# GSM_PPS_LED_Driver.net
KiCad netlist of a schematic drawn in Altium Designer
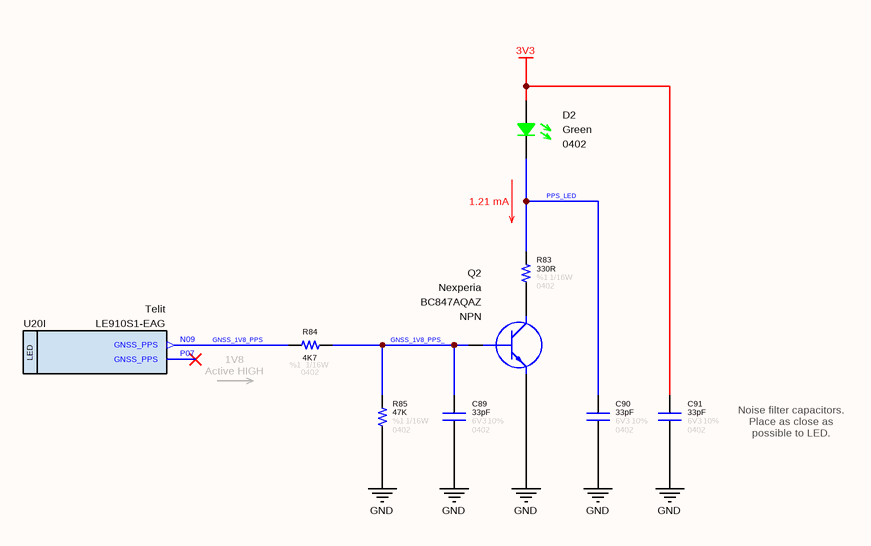
[diagram p0: GSM PPS LED Driver.SchDoc]

(export (version "E")
  (design (tool "Eeschema 10.0.6"))
  (components
    (comp (ref "C89")
      (value "33pF")
      (footprint "CAPACITOR_0402")
      (description "Capacitor - 33pF [0402] (Ceramic)")
      (fields
        (field (name "MANUFACTURER PART NUMBER") "C0402C330J9RACAUTO")
        (field (name "TOLERANCE") "10%")
        (field (name "CASE") "0402")
        (field (name "VOLTAGE") "6V3")
      )
      (libsource (lib "Akkoyun") (part "Capacitor - 33pF [0402-6V3]"))
    )
    (comp (ref "C90")
      (value "33pF")
      (footprint "CAPACITOR_0402")
      (description "Capacitor - 33pF [0402] (Ceramic)")
      (fields
        (field (name "MANUFACTURER PART NUMBER") "C0402C330J9RACAUTO")
        (field (name "TOLERANCE") "10%")
        (field (name "CASE") "0402")
        (field (name "VOLTAGE") "6V3")
      )
      (libsource (lib "Akkoyun") (part "Capacitor - 33pF [0402-6V3]"))
    )
    (comp (ref "C91")
      (value "33pF")
      (footprint "CAPACITOR_0402")
      (description "Capacitor - 33pF [0402] (Ceramic)")
      (fields
        (field (name "MANUFACTURER PART NUMBER") "C0402C330J9RACAUTO")
        (field (name "TOLERANCE") "10%")
        (field (name "CASE") "0402")
        (field (name "VOLTAGE") "6V3")
      )
      (libsource (lib "Akkoyun") (part "Capacitor - 33pF [0402-6V3]"))
    )
    (comp (ref "D2")
      (value "SMD LED (Green)")
      (footprint "LED_0402")
      (description "Standard LEDs - SMD MINI-MOLD ULTRA COMPACT GREEN")
      (fields
        (field (name "MANUFACTURER PART NUMBER") "SML-P12MTT86R")
        (field (name "CASE") "0402")
        (field (name "COLOR") "Green")
      )
      (libsource (lib "Akkoyun") (part "Diode - LED (0402-Green)"))
    )
    (comp (ref "Q2")
      (value "BC847AQAZ")
      (footprint "SOT1215")
      (description "Bipolar NPN Transistors")
      (fields
        (field (name "MANUFACTURER NAME") "Nexperia")
        (field (name "MANUFACTURER PART NUMBER") "BC847AQAZ")
        (field (name "POLARITY") "NPN")
      )
      (libsource (lib "Akkoyun") (part "Transistor - BC847"))
    )
    (comp (ref "R83")
      (value "330R")
      (footprint "RESISTOR_0402")
      (description "Thick Film Resistors - SMD 1/16 W 330 Ohm 1%")
      (fields
        (field (name "MANUFACTURER PART NUMBER") "CRCW0402330RFKED")
        (field (name "CASE") "0402")
        (field (name "TOLERANCE") "%1")
        (field (name "POWER") "1/16W")
        (field (name "Comment") "330R - 0402 - %1 - 1/16W")
      )
      (libsource (lib "Akkoyun") (part "Resistor - 330R [0402]"))
    )
    (comp (ref "R84")
      (value "4K7")
      (footprint "RESISTOR_0402")
      (description "Thick Film Resistors - SMD 1/16 W 4.7 KOhm 1%")
      (fields
        (field (name "MANUFACTURER PART NUMBER") "CRCW04024K70FKED")
        (field (name "TOLERANCE") "%1")
        (field (name "CASE") "0402")
        (field (name "POWER") "1/16W")
        (field (name "Comment") "4K7 - 0402 - %1 - 1/16W")
      )
      (libsource (lib "Akkoyun") (part "Resistor - 4K7 [0402]"))
    )
    (comp (ref "R85")
      (value "47K")
      (footprint "RESISTOR_0402")
      (description "Thick Film Resistors - SMD 1/16 W 47 KOhm 1%")
      (fields
        (field (name "MANUFACTURER PART NUMBER") "CRCW040247K0FKED")
        (field (name "TOLERANCE") "%1")
        (field (name "CASE") "0402")
        (field (name "POWER") "1/16W")
        (field (name "Comment") "47K - 0402 - %1 - 1/16W")
      )
      (libsource (lib "Akkoyun") (part "Resistor - 47K [0402]"))
    )
    (comp (ref "U20")
      (value "LE910S1-EAG LTE GSM Module")
      (footprint "LE910 GSM Modem")
      (description "Telit LE910S1-EAG GPRS/GNSS Module")
      (fields
        (field (name "MANUFACTURER PART NUMBER") "LE910S1-EAG")
        (field (name "MANUFACTURER NAME") "Telit")
      )
      (libsource (lib "Akkoyun") (part "IC - LE910S1-EAG"))
    )
  )
  (nets
    (net (code "1") (name "/GNSS_1V8_PPS") (class "Default")
      (node (ref "R84") (pin "2") (pinfunction "2_2") (pintype "passive"))
      (node (ref "U20") (pin "N09") (pinfunction "GNSS_PPS_N09") (pintype "output"))
    )
    (net (code "2") (name "/GNSS_1V8_PPS_") (class "Default")
      (node (ref "C89") (pin "2") (pinfunction "2_2") (pintype "passive"))
      (node (ref "Q2") (pin "1") (pinfunction "B_1") (pintype "passive"))
      (node (ref "R84") (pin "1") (pinfunction "1_1") (pintype "passive"))
      (node (ref "R85") (pin "2") (pinfunction "2_2") (pintype "passive"))
    )
    (net (code "3") (name "/PPS_LED") (class "Default")
      (node (ref "C90") (pin "2") (pinfunction "2_2") (pintype "passive"))
      (node (ref "D2") (pin "1") (pinfunction "1_1") (pintype "passive"))
      (node (ref "R83") (pin "2") (pinfunction "2_2") (pintype "passive"))
    )
    (net (code "4") (name "3V3") (class "Default")
      (node (ref "C91") (pin "2") (pinfunction "2_2") (pintype "passive"))
      (node (ref "D2") (pin "2") (pinfunction "2_2") (pintype "passive"))
    )
    (net (code "5") (name "GND") (class "Default")
      (node (ref "C89") (pin "1") (pinfunction "1_1") (pintype "passive"))
      (node (ref "C90") (pin "1") (pinfunction "1_1") (pintype "passive"))
      (node (ref "C91") (pin "1") (pinfunction "1_1") (pintype "passive"))
      (node (ref "Q2") (pin "2") (pinfunction "E_2") (pintype "passive"))
      (node (ref "R85") (pin "1") (pinfunction "1_1") (pintype "passive"))
    )
    (net (code "6") (name "Net-(Q2-C)") (class "Default")
      (node (ref "Q2") (pin "3") (pinfunction "C_3") (pintype "passive"))
      (node (ref "R83") (pin "1") (pinfunction "1_1") (pintype "passive"))
    )
    (net (code "7") (name "unconnected-(U20I-GNSS_PPS-PadP07)") (class "Default")
      (node (ref "U20") (pin "P07") (pinfunction "GNSS_PPS_P07") (pintype "passive+no_connect"))
    )
  )
)
